# Yitran_IT900_Hutschiene_PIM7A_908_1_4_un.net
KiCad netlist of a schematic drawn in Altium Designer
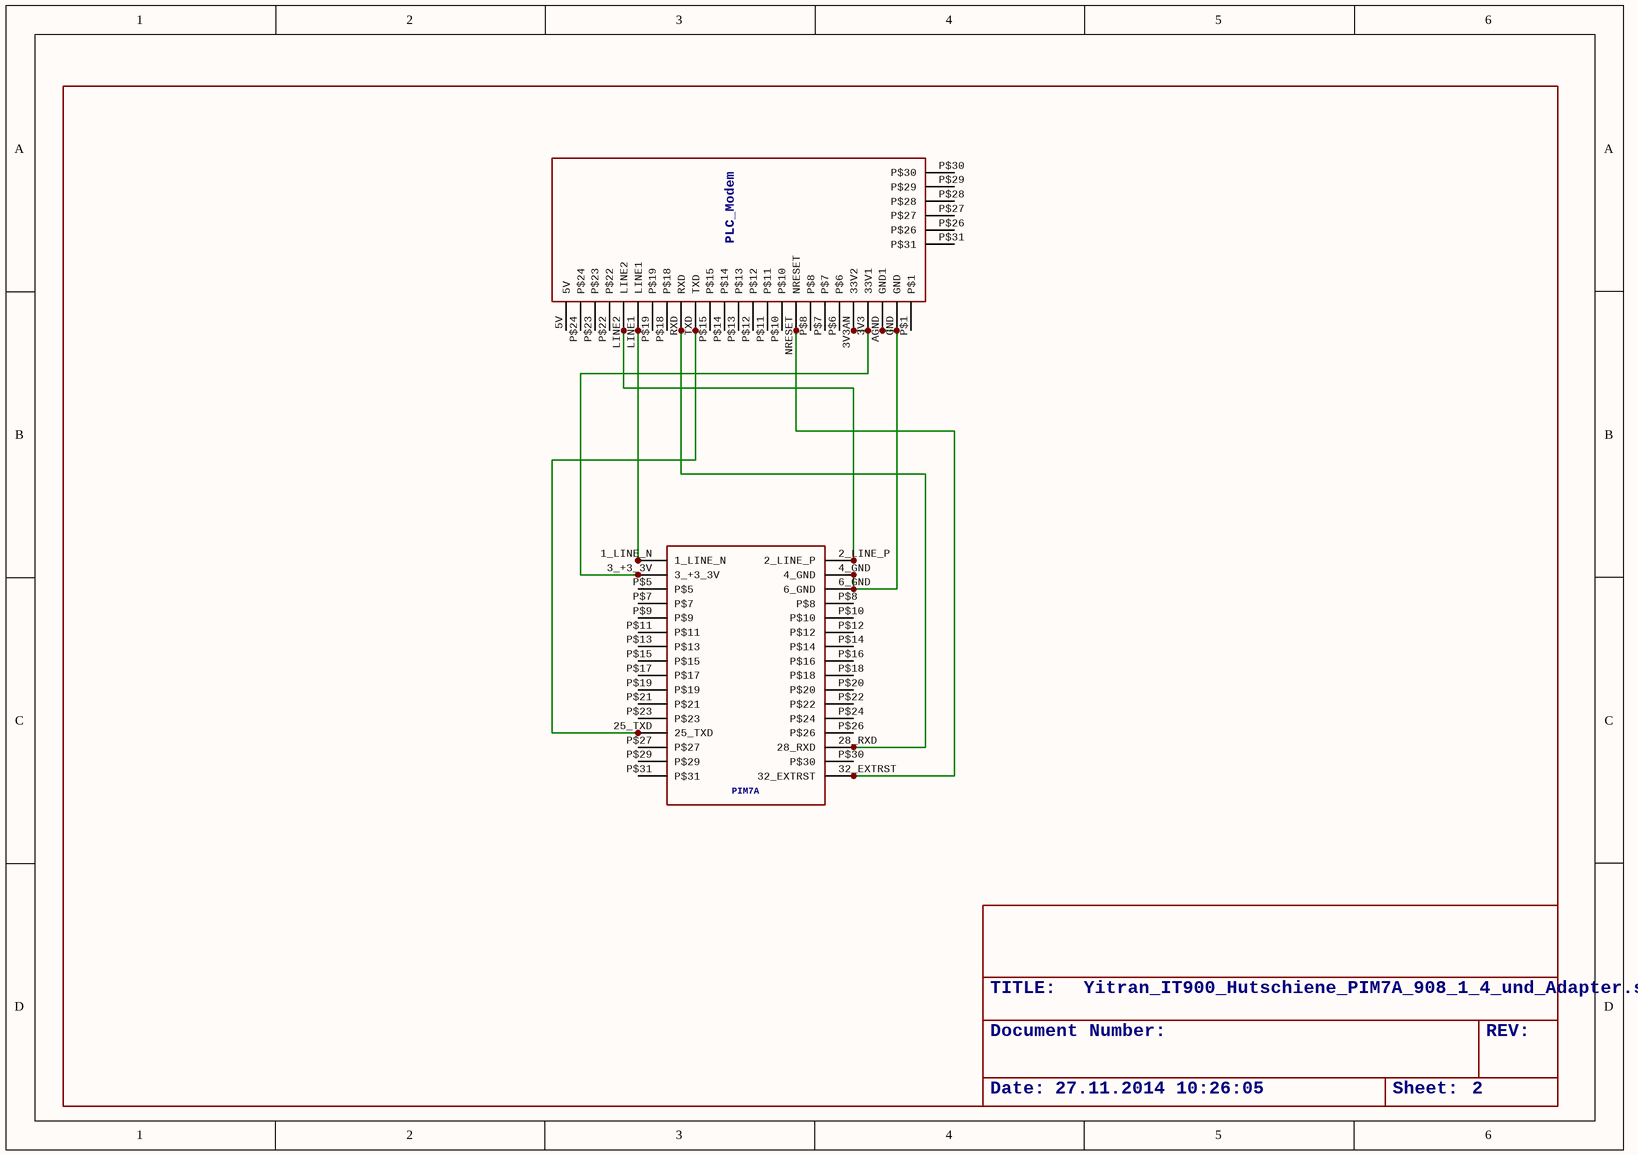
[diagram p0: Yitran_IT900_Hutschiene_PIM7A_908_1_4_und_Adapter_1.SchDoc]

(export (version "E")
  (design (tool "Eeschema 10.0.6"))
  (components
    (comp (ref "FRAME2")
      (value "DINA4_L")
      (description "<b>FRAME</b><p>\nDIN A4, landscape with extra doc field")
      (fields
        (field (name "DATE:") "Date:")
        (field (name ">LAST_DATE_TIME") "27.11.2014 10:26:05")
        (field (name "SHEET:") "Sheet:")
        (field (name ">SHEET") "2")
        (field (name "REV:") "REV:")
        (field (name "TITLE:") "TITLE:")
        (field (name "DOCUMENT NUMBER:") "Document Number:")
        (field (name ">DRAWING_NAME") "Yitran_IT900_Hutschiene_PIM7A_908_1_4_und_Adapter.sch")
      )
      (libsource (lib "frames") (part "DINA4_L"))
    )
    (comp (ref "U$5")
      (value "MODEMSTECKER_KLEINE_PINS")
      (footprint "MODEM_FUSS_KLEINE_PINS")
      (fields (field (name "PLC_MODEM") "PLC_Modem"))
      (libsource (lib "ADS1") (part "MODEMSTECKER_KLEINE_PINS"))
    )
    (comp (ref "U$6")
      (value "IT900PIM7A")
      (footprint "IT900PIM7A")
      (fields (field (name "PIM7A") "PIM7A"))
      (libsource (lib "ADS1") (part "IT900PIM7A"))
    )
  )
  (nets
    (net (code "1") (name "Net-(U$5-33V1)") (class "Default")
      (node (ref "U$5") (pin "3V3") (pinfunction "33V1_3V3") (pintype "passive"))
      (node (ref "U$5") (pin "3V3AN") (pinfunction "33V2_3V3AN") (pintype "passive"))
      (node (ref "U$6") (pin "3_+3_3V") (pinfunction "3_+3_3V_3_+3_3V") (pintype "passive"))
    )
    (net (code "2") (name "Net-(U$5-GND1)") (class "Default")
      (node (ref "U$5") (pin "AGND") (pinfunction "GND1_AGND") (pintype "passive"))
      (node (ref "U$5") (pin "GND") (pinfunction "GND_GND") (pintype "passive"))
      (node (ref "U$6") (pin "4_GND") (pinfunction "4_GND_4_GND") (pintype "passive"))
      (node (ref "U$6") (pin "6_GND") (pinfunction "6_GND_6_GND") (pintype "passive"))
    )
    (net (code "3") (name "Net-(U$5-PadLINE1)") (class "Default")
      (node (ref "U$5") (pin "LINE1") (pinfunction "LINE1_LINE1") (pintype "passive"))
      (node (ref "U$6") (pin "1_LINE_N") (pinfunction "1_LINE_N_1_LINE_N") (pintype "passive"))
    )
    (net (code "4") (name "Net-(U$5-PadLINE2)") (class "Default")
      (node (ref "U$5") (pin "LINE2") (pinfunction "LINE2_LINE2") (pintype "passive"))
      (node (ref "U$6") (pin "2_LINE_P") (pinfunction "2_LINE_P_2_LINE_P") (pintype "passive"))
    )
    (net (code "5") (name "Net-(U$5-PadNRESET)") (class "Default")
      (node (ref "U$5") (pin "NRESET") (pinfunction "NRESET_NRESET") (pintype "passive"))
      (node (ref "U$6") (pin "32_EXTRST") (pinfunction "32_EXTRST_32_EXTRST") (pintype "passive"))
    )
    (net (code "6") (name "Net-(U$5-PadRXD)") (class "Default")
      (node (ref "U$5") (pin "RXD") (pinfunction "RXD_RXD") (pintype "passive"))
      (node (ref "U$6") (pin "28_RXD") (pinfunction "28_RXD_28_RXD") (pintype "passive"))
    )
    (net (code "7") (name "Net-(U$5-PadTXD)") (class "Default")
      (node (ref "U$5") (pin "TXD") (pinfunction "TXD_TXD") (pintype "passive"))
      (node (ref "U$6") (pin "25_TXD") (pinfunction "25_TXD_25_TXD") (pintype "passive"))
    )
    (net (code "8") (name "unconnected-(U$5-Pad5V)") (class "Default")
      (node (ref "U$5") (pin "5V") (pinfunction "5V_5V") (pintype "passive"))
    )
    (net (code "9") (name "unconnected-(U$5-PadP$1)") (class "Default")
      (node (ref "U$5") (pin "P$1") (pinfunction "P$1_P$1") (pintype "passive"))
    )
    (net (code "10") (name "unconnected-(U$5-PadP$6)") (class "Default")
      (node (ref "U$5") (pin "P$6") (pinfunction "P$6_P$6") (pintype "passive"))
    )
    (net (code "11") (name "unconnected-(U$5-PadP$7)") (class "Default")
      (node (ref "U$5") (pin "P$7") (pinfunction "P$7_P$7") (pintype "passive"))
    )
    (net (code "12") (name "unconnected-(U$5-PadP$8)") (class "Default")
      (node (ref "U$5") (pin "P$8") (pinfunction "P$8_P$8") (pintype "passive"))
    )
    (net (code "13") (name "unconnected-(U$5-PadP$10)") (class "Default")
      (node (ref "U$5") (pin "P$10") (pinfunction "P$10_P$10") (pintype "passive"))
    )
    (net (code "14") (name "unconnected-(U$5-PadP$11)") (class "Default")
      (node (ref "U$5") (pin "P$11") (pinfunction "P$11_P$11") (pintype "passive"))
    )
    (net (code "15") (name "unconnected-(U$5-PadP$12)") (class "Default")
      (node (ref "U$5") (pin "P$12") (pinfunction "P$12_P$12") (pintype "passive"))
    )
    (net (code "16") (name "unconnected-(U$5-PadP$13)") (class "Default")
      (node (ref "U$5") (pin "P$13") (pinfunction "P$13_P$13") (pintype "passive"))
    )
    (net (code "17") (name "unconnected-(U$5-PadP$14)") (class "Default")
      (node (ref "U$5") (pin "P$14") (pinfunction "P$14_P$14") (pintype "passive"))
    )
    (net (code "18") (name "unconnected-(U$5-PadP$15)") (class "Default")
      (node (ref "U$5") (pin "P$15") (pinfunction "P$15_P$15") (pintype "passive"))
    )
    (net (code "19") (name "unconnected-(U$5-PadP$18)") (class "Default")
      (node (ref "U$5") (pin "P$18") (pinfunction "P$18_P$18") (pintype "passive"))
    )
    (net (code "20") (name "unconnected-(U$5-PadP$19)") (class "Default")
      (node (ref "U$5") (pin "P$19") (pinfunction "P$19_P$19") (pintype "passive"))
    )
    (net (code "21") (name "unconnected-(U$5-PadP$22)") (class "Default")
      (node (ref "U$5") (pin "P$22") (pinfunction "P$22_P$22") (pintype "passive"))
    )
    (net (code "22") (name "unconnected-(U$5-PadP$23)") (class "Default")
      (node (ref "U$5") (pin "P$23") (pinfunction "P$23_P$23") (pintype "passive"))
    )
    (net (code "23") (name "unconnected-(U$5-PadP$24)") (class "Default")
      (node (ref "U$5") (pin "P$24") (pinfunction "P$24_P$24") (pintype "passive"))
    )
    (net (code "24") (name "unconnected-(U$5-PadP$26)") (class "Default")
      (node (ref "U$5") (pin "P$26") (pinfunction "P$26_P$26") (pintype "passive"))
    )
    (net (code "25") (name "unconnected-(U$5-PadP$27)") (class "Default")
      (node (ref "U$5") (pin "P$27") (pinfunction "P$27_P$27") (pintype "passive"))
    )
    (net (code "26") (name "unconnected-(U$5-PadP$28)") (class "Default")
      (node (ref "U$5") (pin "P$28") (pinfunction "P$28_P$28") (pintype "passive"))
    )
    (net (code "27") (name "unconnected-(U$5-PadP$29)") (class "Default")
      (node (ref "U$5") (pin "P$29") (pinfunction "P$29_P$29") (pintype "passive"))
    )
    (net (code "28") (name "unconnected-(U$5-PadP$30)") (class "Default")
      (node (ref "U$5") (pin "P$30") (pinfunction "P$30_P$30") (pintype "passive"))
    )
    (net (code "29") (name "unconnected-(U$5-PadP$31)") (class "Default")
      (node (ref "U$5") (pin "P$31") (pinfunction "P$31_P$31") (pintype "passive"))
    )
    (net (code "30") (name "unconnected-(U$6-PadP$5)") (class "Default")
      (node (ref "U$6") (pin "P$5") (pinfunction "P$5_P$5") (pintype "passive"))
    )
    (net (code "31") (name "unconnected-(U$6-PadP$7)") (class "Default")
      (node (ref "U$6") (pin "P$7") (pinfunction "P$7_P$7") (pintype "passive"))
    )
    (net (code "32") (name "unconnected-(U$6-PadP$8)") (class "Default")
      (node (ref "U$6") (pin "P$8") (pinfunction "P$8_P$8") (pintype "passive"))
    )
    (net (code "33") (name "unconnected-(U$6-PadP$9)") (class "Default")
      (node (ref "U$6") (pin "P$9") (pinfunction "P$9_P$9") (pintype "passive"))
    )
    (net (code "34") (name "unconnected-(U$6-PadP$10)") (class "Default")
      (node (ref "U$6") (pin "P$10") (pinfunction "P$10_P$10") (pintype "passive"))
    )
    (net (code "35") (name "unconnected-(U$6-PadP$11)") (class "Default")
      (node (ref "U$6") (pin "P$11") (pinfunction "P$11_P$11") (pintype "passive"))
    )
    (net (code "36") (name "unconnected-(U$6-PadP$12)") (class "Default")
      (node (ref "U$6") (pin "P$12") (pinfunction "P$12_P$12") (pintype "passive"))
    )
    (net (code "37") (name "unconnected-(U$6-PadP$13)") (class "Default")
      (node (ref "U$6") (pin "P$13") (pinfunction "P$13_P$13") (pintype "passive"))
    )
    (net (code "38") (name "unconnected-(U$6-PadP$14)") (class "Default")
      (node (ref "U$6") (pin "P$14") (pinfunction "P$14_P$14") (pintype "passive"))
    )
    (net (code "39") (name "unconnected-(U$6-PadP$15)") (class "Default")
      (node (ref "U$6") (pin "P$15") (pinfunction "P$15_P$15") (pintype "passive"))
    )
    (net (code "40") (name "unconnected-(U$6-PadP$16)") (class "Default")
      (node (ref "U$6") (pin "P$16") (pinfunction "P$16_P$16") (pintype "passive"))
    )
    (net (code "41") (name "unconnected-(U$6-PadP$17)") (class "Default")
      (node (ref "U$6") (pin "P$17") (pinfunction "P$17_P$17") (pintype "passive"))
    )
    (net (code "42") (name "unconnected-(U$6-PadP$18)") (class "Default")
      (node (ref "U$6") (pin "P$18") (pinfunction "P$18_P$18") (pintype "passive"))
    )
    (net (code "43") (name "unconnected-(U$6-PadP$19)") (class "Default")
      (node (ref "U$6") (pin "P$19") (pinfunction "P$19_P$19") (pintype "passive"))
    )
    (net (code "44") (name "unconnected-(U$6-PadP$20)") (class "Default")
      (node (ref "U$6") (pin "P$20") (pinfunction "P$20_P$20") (pintype "passive"))
    )
    (net (code "45") (name "unconnected-(U$6-PadP$21)") (class "Default")
      (node (ref "U$6") (pin "P$21") (pinfunction "P$21_P$21") (pintype "passive"))
    )
    (net (code "46") (name "unconnected-(U$6-PadP$22)") (class "Default")
      (node (ref "U$6") (pin "P$22") (pinfunction "P$22_P$22") (pintype "passive"))
    )
    (net (code "47") (name "unconnected-(U$6-PadP$23)") (class "Default")
      (node (ref "U$6") (pin "P$23") (pinfunction "P$23_P$23") (pintype "passive"))
    )
    (net (code "48") (name "unconnected-(U$6-PadP$24)") (class "Default")
      (node (ref "U$6") (pin "P$24") (pinfunction "P$24_P$24") (pintype "passive"))
    )
    (net (code "49") (name "unconnected-(U$6-PadP$26)") (class "Default")
      (node (ref "U$6") (pin "P$26") (pinfunction "P$26_P$26") (pintype "passive"))
    )
    (net (code "50") (name "unconnected-(U$6-PadP$27)") (class "Default")
      (node (ref "U$6") (pin "P$27") (pinfunction "P$27_P$27") (pintype "passive"))
    )
    (net (code "51") (name "unconnected-(U$6-PadP$29)") (class "Default")
      (node (ref "U$6") (pin "P$29") (pinfunction "P$29_P$29") (pintype "passive"))
    )
    (net (code "52") (name "unconnected-(U$6-PadP$30)") (class "Default")
      (node (ref "U$6") (pin "P$30") (pinfunction "P$30_P$30") (pintype "passive"))
    )
    (net (code "53") (name "unconnected-(U$6-PadP$31)") (class "Default")
      (node (ref "U$6") (pin "P$31") (pinfunction "P$31_P$31") (pintype "passive"))
    )
  )
)
